# gol.net
KiCad netlist of a schematic drawn in EAGLE
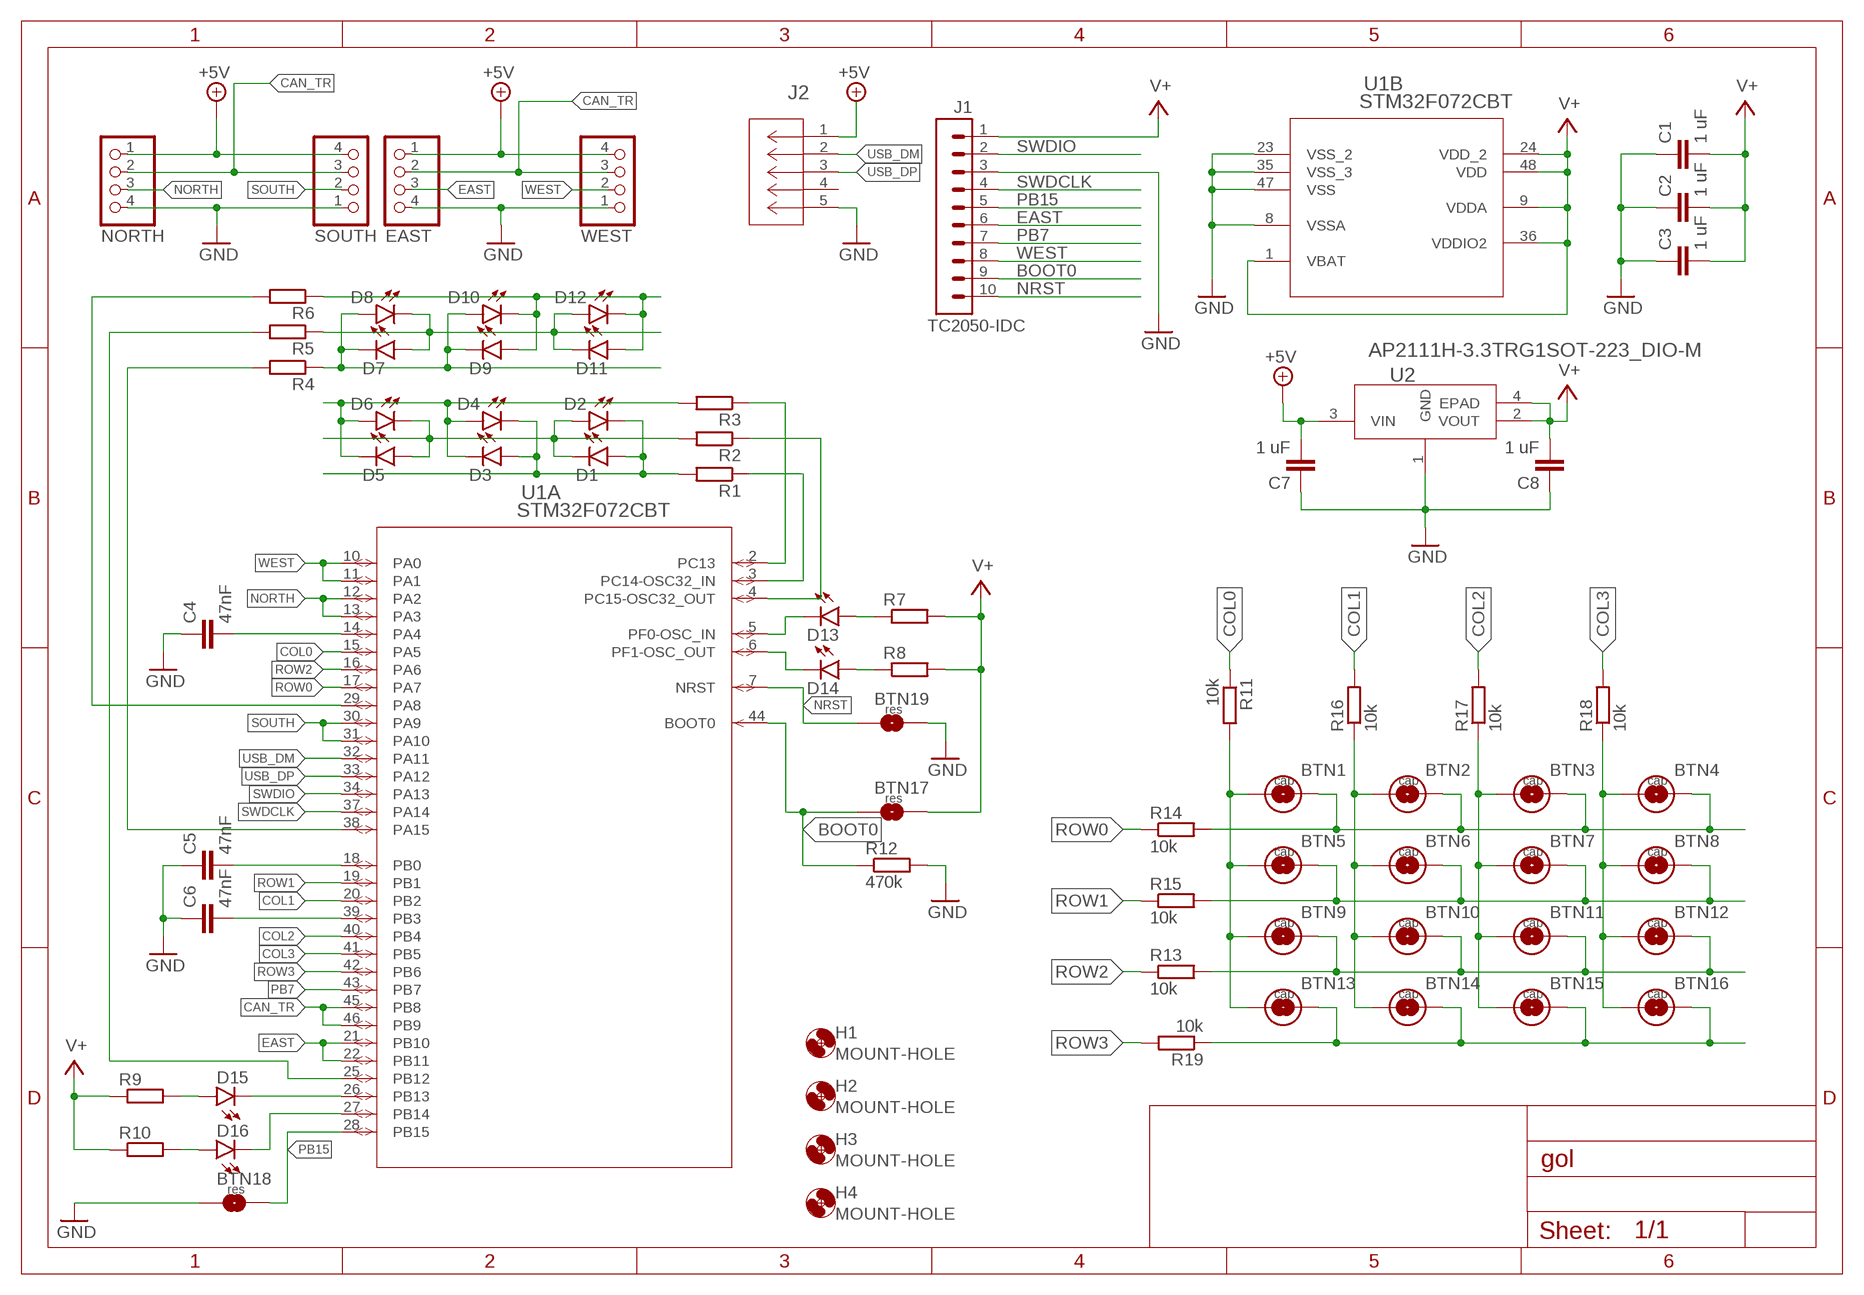
[diagram p0: schematic, sheet 1]

(export (version "E")
  (design (tool "Eeschema 10.0.6"))
  (components
    (comp (ref "BTN1")
      (value "BUTTON-CAP")
      (footprint "eagle-import:COMB")
      (libsource (lib "eagle-import") (part "BUTTON-CAP"))
    )
    (comp (ref "BTN2")
      (value "BUTTON-CAP")
      (footprint "eagle-import:COMB")
      (libsource (lib "eagle-import") (part "BUTTON-CAP"))
    )
    (comp (ref "BTN3")
      (value "BUTTON-CAP")
      (footprint "eagle-import:COMB")
      (libsource (lib "eagle-import") (part "BUTTON-CAP"))
    )
    (comp (ref "BTN4")
      (value "BUTTON-CAP")
      (footprint "eagle-import:COMB")
      (libsource (lib "eagle-import") (part "BUTTON-CAP"))
    )
    (comp (ref "BTN5")
      (value "BUTTON-CAP")
      (footprint "eagle-import:COMB")
      (libsource (lib "eagle-import") (part "BUTTON-CAP"))
    )
    (comp (ref "BTN6")
      (value "BUTTON-CAP")
      (footprint "eagle-import:COMB")
      (libsource (lib "eagle-import") (part "BUTTON-CAP"))
    )
    (comp (ref "BTN7")
      (value "BUTTON-CAP")
      (footprint "eagle-import:COMB")
      (libsource (lib "eagle-import") (part "BUTTON-CAP"))
    )
    (comp (ref "BTN8")
      (value "BUTTON-CAP")
      (footprint "eagle-import:COMB")
      (libsource (lib "eagle-import") (part "BUTTON-CAP"))
    )
    (comp (ref "BTN9")
      (value "BUTTON-CAP")
      (footprint "eagle-import:COMB")
      (libsource (lib "eagle-import") (part "BUTTON-CAP"))
    )
    (comp (ref "BTN10")
      (value "BUTTON-CAP")
      (footprint "eagle-import:COMB")
      (libsource (lib "eagle-import") (part "BUTTON-CAP"))
    )
    (comp (ref "BTN11")
      (value "BUTTON-CAP")
      (footprint "eagle-import:COMB")
      (libsource (lib "eagle-import") (part "BUTTON-CAP"))
    )
    (comp (ref "BTN12")
      (value "BUTTON-CAP")
      (footprint "eagle-import:COMB")
      (libsource (lib "eagle-import") (part "BUTTON-CAP"))
    )
    (comp (ref "BTN13")
      (value "BUTTON-CAP")
      (footprint "eagle-import:COMB")
      (libsource (lib "eagle-import") (part "BUTTON-CAP"))
    )
    (comp (ref "BTN14")
      (value "BUTTON-CAP")
      (footprint "eagle-import:COMB")
      (libsource (lib "eagle-import") (part "BUTTON-CAP"))
    )
    (comp (ref "BTN15")
      (value "BUTTON-CAP")
      (footprint "eagle-import:COMB")
      (libsource (lib "eagle-import") (part "BUTTON-CAP"))
    )
    (comp (ref "BTN16")
      (value "BUTTON-CAP")
      (footprint "eagle-import:COMB")
      (libsource (lib "eagle-import") (part "BUTTON-CAP"))
    )
    (comp (ref "BTN17")
      (value "FLASH")
      (footprint "eagle-import:COMB_EXPOSED")
      (libsource (lib "eagle-import") (part "BUTTON-RES"))
    )
    (comp (ref "BTN18")
      (value "MENU")
      (footprint "eagle-import:COMB_EXPOSED")
      (libsource (lib "eagle-import") (part "BUTTON-RES"))
    )
    (comp (ref "BTN19")
      (value "RESET")
      (footprint "eagle-import:COMB_EXPOSED")
      (libsource (lib "eagle-import") (part "BUTTON-RES"))
    )
    (comp (ref "C1")
      (value "1 uF")
      (footprint "eagle-import:C0603")
      (libsource (lib "eagle-import") (part "C-EUC0603"))
    )
    (comp (ref "C2")
      (value "1 uF")
      (footprint "eagle-import:C0603")
      (libsource (lib "eagle-import") (part "C-EUC0603"))
    )
    (comp (ref "C3")
      (value "1 uF")
      (footprint "eagle-import:C0603")
      (libsource (lib "eagle-import") (part "C-EUC0603"))
    )
    (comp (ref "C4")
      (value "47nF")
      (footprint "eagle-import:C0603")
      (libsource (lib "eagle-import") (part "C-EUC0603"))
    )
    (comp (ref "C5")
      (value "47nF")
      (footprint "eagle-import:C0603")
      (libsource (lib "eagle-import") (part "C-EUC0603"))
    )
    (comp (ref "C6")
      (value "47nF")
      (footprint "eagle-import:C0603")
      (libsource (lib "eagle-import") (part "C-EUC0603"))
    )
    (comp (ref "C7")
      (value "1 uF")
      (footprint "eagle-import:C0603")
      (libsource (lib "eagle-import") (part "C-EUC0603"))
    )
    (comp (ref "C8")
      (value "1 uF")
      (footprint "eagle-import:C0603")
      (libsource (lib "eagle-import") (part "C-EUC0603"))
    )
    (comp (ref "D1")
      (value "LED-5MM")
      (footprint "eagle-import:LED5MM")
      (libsource (lib "eagle-import") (part "LED-5MM"))
    )
    (comp (ref "D2")
      (value "LED-5MM")
      (footprint "eagle-import:LED5MM")
      (libsource (lib "eagle-import") (part "LED-5MM"))
    )
    (comp (ref "D3")
      (value "LED-5MM")
      (footprint "eagle-import:LED5MM")
      (libsource (lib "eagle-import") (part "LED-5MM"))
    )
    (comp (ref "D4")
      (value "LED-5MM")
      (footprint "eagle-import:LED5MM")
      (libsource (lib "eagle-import") (part "LED-5MM"))
    )
    (comp (ref "D5")
      (value "LED-5MM")
      (footprint "eagle-import:LED5MM")
      (libsource (lib "eagle-import") (part "LED-5MM"))
    )
    (comp (ref "D6")
      (value "LED-5MM")
      (footprint "eagle-import:LED5MM")
      (libsource (lib "eagle-import") (part "LED-5MM"))
    )
    (comp (ref "D7")
      (value "LED-5MM")
      (footprint "eagle-import:LED5MM")
      (libsource (lib "eagle-import") (part "LED-5MM"))
    )
    (comp (ref "D8")
      (value "LED-5MM")
      (footprint "eagle-import:LED5MM")
      (libsource (lib "eagle-import") (part "LED-5MM"))
    )
    (comp (ref "D9")
      (value "LED-5MM")
      (footprint "eagle-import:LED5MM")
      (libsource (lib "eagle-import") (part "LED-5MM"))
    )
    (comp (ref "D10")
      (value "LED-5MM")
      (footprint "eagle-import:LED5MM")
      (libsource (lib "eagle-import") (part "LED-5MM"))
    )
    (comp (ref "D11")
      (value "LED-5MM")
      (footprint "eagle-import:LED5MM")
      (libsource (lib "eagle-import") (part "LED-5MM"))
    )
    (comp (ref "D12")
      (value "LED-5MM")
      (footprint "eagle-import:LED5MM")
      (libsource (lib "eagle-import") (part "LED-5MM"))
    )
    (comp (ref "D13")
      (value "LED-5MM")
      (footprint "eagle-import:LED5MM")
      (libsource (lib "eagle-import") (part "LED-5MM"))
    )
    (comp (ref "D14")
      (value "LED-5MM")
      (footprint "eagle-import:LED5MM")
      (libsource (lib "eagle-import") (part "LED-5MM"))
    )
    (comp (ref "D15")
      (value "LED-5MM")
      (footprint "eagle-import:LED5MM")
      (libsource (lib "eagle-import") (part "LED-5MM"))
    )
    (comp (ref "D16")
      (value "LED-5MM")
      (footprint "eagle-import:LED5MM")
      (libsource (lib "eagle-import") (part "LED-5MM"))
    )
    (comp (ref "EAST")
      (value "EAST")
      (footprint "eagle-import:1X04")
      (libsource (lib "eagle-import") (part "PINHD-1X04"))
    )
    (comp (ref "H1")
      (value "MOUNT-HOLE")
      (footprint "eagle-import:MOUNT-HOLE-2,8")
      (libsource (lib "eagle-import") (part "MOUNT-HOLE"))
    )
    (comp (ref "H2")
      (value "MOUNT-HOLE")
      (footprint "eagle-import:MOUNT-HOLE-2,8")
      (libsource (lib "eagle-import") (part "MOUNT-HOLE"))
    )
    (comp (ref "H3")
      (value "MOUNT-HOLE")
      (footprint "eagle-import:MOUNT-HOLE-2,8")
      (libsource (lib "eagle-import") (part "MOUNT-HOLE"))
    )
    (comp (ref "H4")
      (value "MOUNT-HOLE")
      (footprint "eagle-import:MOUNT-HOLE-2,8")
      (libsource (lib "eagle-import") (part "MOUNT-HOLE"))
    )
    (comp (ref "J1")
      (value "TC2050-IDC")
      (footprint "eagle-import:TC2050-IDC")
      (libsource (lib "eagle-import") (part "TC2050-IDC"))
    )
    (comp (ref "J2")
      (value "2057-MCR-B-S-RA-TSMT-NP-CS4-T/RCT-ND")
      (footprint "eagle-import:CONN_10118192-0002LF_AMP")
      (fields
        (field (name "MANUFACTURER_PART_NUMBER") "10118192-0002LF")
        (field (name "COPYRIGHT") "Copyright (C) 2023 Ultra Librarian. All rights reserved.")
      )
      (libsource (lib "eagle-import") (part "10118192-0002LFCONN_10118192-0002LF_AMP"))
    )
    (comp (ref "NORTH")
      (value "NORTH")
      (footprint "eagle-import:JP4-RA-FEM")
      (libsource (lib "eagle-import") (part "PINHD-1X041X04-RA-FEM"))
    )
    (comp (ref "R1")
      (value "R-EU-0207/8")
      (footprint "eagle-import:0207_8")
      (libsource (lib "eagle-import") (part "R-EU-0207/8"))
    )
    (comp (ref "R2")
      (value "R-EU-0207/8")
      (footprint "eagle-import:0207_8")
      (libsource (lib "eagle-import") (part "R-EU-0207/8"))
    )
    (comp (ref "R3")
      (value "R-EU-0207/8")
      (footprint "eagle-import:0207_8")
      (libsource (lib "eagle-import") (part "R-EU-0207/8"))
    )
    (comp (ref "R4")
      (value "R-EU-0207/8")
      (footprint "eagle-import:0207_8")
      (libsource (lib "eagle-import") (part "R-EU-0207/8"))
    )
    (comp (ref "R5")
      (value "R-EU-0207/8")
      (footprint "eagle-import:0207_8")
      (libsource (lib "eagle-import") (part "R-EU-0207/8"))
    )
    (comp (ref "R6")
      (value "R-EU-0207/8")
      (footprint "eagle-import:0207_8")
      (libsource (lib "eagle-import") (part "R-EU-0207/8"))
    )
    (comp (ref "R7")
      (value "R-EU-0207/8")
      (footprint "eagle-import:0207_8")
      (libsource (lib "eagle-import") (part "R-EU-0207/8"))
    )
    (comp (ref "R8")
      (value "R-EU-0207/8")
      (footprint "eagle-import:0207_8")
      (libsource (lib "eagle-import") (part "R-EU-0207/8"))
    )
    (comp (ref "R9")
      (value "R-EU-0207/8")
      (footprint "eagle-import:0207_8")
      (libsource (lib "eagle-import") (part "R-EU-0207/8"))
    )
    (comp (ref "R10")
      (value "R-EU-0207/8")
      (footprint "eagle-import:0207_8")
      (libsource (lib "eagle-import") (part "R-EU-0207/8"))
    )
    (comp (ref "R11")
      (value "10k")
      (footprint "eagle-import:R0603")
      (libsource (lib "eagle-import") (part "R-EU_R0603"))
    )
    (comp (ref "R12")
      (value "470k")
      (footprint "eagle-import:R0603")
      (libsource (lib "eagle-import") (part "R-EU_R0603"))
    )
    (comp (ref "R13")
      (value "10k")
      (footprint "eagle-import:R0603")
      (libsource (lib "eagle-import") (part "R-EU_R0603"))
    )
    (comp (ref "R14")
      (value "10k")
      (footprint "eagle-import:R0603")
      (libsource (lib "eagle-import") (part "R-EU_R0603"))
    )
    (comp (ref "R15")
      (value "10k")
      (footprint "eagle-import:R0603")
      (libsource (lib "eagle-import") (part "R-EU_R0603"))
    )
    (comp (ref "R16")
      (value "10k")
      (footprint "eagle-import:R0603")
      (libsource (lib "eagle-import") (part "R-EU_R0603"))
    )
    (comp (ref "R17")
      (value "10k")
      (footprint "eagle-import:R0603")
      (libsource (lib "eagle-import") (part "R-EU_R0603"))
    )
    (comp (ref "R18")
      (value "10k")
      (footprint "eagle-import:R0603")
      (libsource (lib "eagle-import") (part "R-EU_R0603"))
    )
    (comp (ref "R19")
      (value "10k")
      (footprint "eagle-import:R0603")
      (libsource (lib "eagle-import") (part "R-EU_R0603"))
    )
    (comp (ref "SOUTH")
      (value "SOUTH")
      (footprint "eagle-import:1X04_90")
      (libsource (lib "eagle-import") (part "PINHD-1X4/90"))
    )
    (comp (ref "U1")
      (value "STM32F072CBT")
      (footprint "eagle-import:LQFP48-7X7MM")
      (fields
        (field (name "MANUFACTURER_PART_NUMBER") "STM32F072CBT6")
        (field (name "COPYRIGHT") "Copyright (C) 2023 Ultra Librarian. All rights reserved.")
      )
      (libsource (lib "eagle-import") (part "STM32F072CBT6LQFP48-7X7MM"))
    )
    (comp (ref "U2")
      (value "AP2111H-3.3TRG1SOT-223_DIO-M")
      (footprint "eagle-import:SOT-223_DIO-M")
      (fields
        (field (name "MANUFACTURER_PART_NUMBER") "AP2111H-3.3TRG1")
        (field (name "COPYRIGHT") "Copyright (C) 2023 Ultra Librarian. All rights reserved.")
      )
      (libsource (lib "eagle-import") (part "AP2111H-3.3TRG1SOT-223_DIO-M"))
    )
    (comp (ref "WEST")
      (value "WEST")
      (footprint "eagle-import:1X04")
      (libsource (lib "eagle-import") (part "PINHD-1X04"))
    )
  )
  (nets
    (net (code "1") (name "+5V") (class "Default")
      (node (ref "C7") (pin "2") (pinfunction "2_2") (pintype "passive"))
      (node (ref "EAST") (pin "1") (pinfunction "1_1") (pintype "passive"))
      (node (ref "J2") (pin "1") (pinfunction "1_1") (pintype "passive"))
      (node (ref "NORTH") (pin "1") (pinfunction "1_1") (pintype "passive"))
      (node (ref "SOUTH") (pin "4") (pinfunction "4_4") (pintype "passive"))
      (node (ref "U2") (pin "3") (pinfunction "VIN_3") (pintype "input"))
      (node (ref "WEST") (pin "4") (pinfunction "4_4") (pintype "passive"))
    )
    (net (code "2") (name "BOOT0") (class "Default")
      (node (ref "BTN17") (pin "P$1") (pinfunction "1_P$1") (pintype "passive"))
      (node (ref "J1") (pin "9") (pinfunction "9_9") (pintype "passive"))
      (node (ref "R12") (pin "1") (pinfunction "1_1") (pintype "passive"))
      (node (ref "U1") (pin "44") (pinfunction "BOOT0_44") (pintype "input"))
    )
    (net (code "3") (name "CAN_TR") (class "Default")
      (node (ref "EAST") (pin "2") (pinfunction "2_2") (pintype "passive"))
      (node (ref "NORTH") (pin "2") (pinfunction "2_2") (pintype "passive"))
      (node (ref "SOUTH") (pin "3") (pinfunction "3_3") (pintype "passive"))
      (node (ref "U1") (pin "45") (pinfunction "PB8_45") (pintype "bidirectional"))
      (node (ref "U1") (pin "46") (pinfunction "PB9_46") (pintype "bidirectional"))
      (node (ref "WEST") (pin "3") (pinfunction "3_3") (pintype "passive"))
    )
    (net (code "4") (name "COL0") (class "Default")
      (node (ref "R11") (pin "1") (pinfunction "1_1") (pintype "passive"))
      (node (ref "U1") (pin "15") (pinfunction "PA5_15") (pintype "bidirectional"))
    )
    (net (code "5") (name "COL1") (class "Default")
      (node (ref "R16") (pin "2") (pinfunction "2_2") (pintype "passive"))
      (node (ref "U1") (pin "20") (pinfunction "PB2_20") (pintype "bidirectional"))
    )
    (net (code "6") (name "COL2") (class "Default")
      (node (ref "R17") (pin "2") (pinfunction "2_2") (pintype "passive"))
      (node (ref "U1") (pin "40") (pinfunction "PB4_40") (pintype "bidirectional"))
    )
    (net (code "7") (name "COL3") (class "Default")
      (node (ref "R18") (pin "2") (pinfunction "2_2") (pintype "passive"))
      (node (ref "U1") (pin "41") (pinfunction "PB5_41") (pintype "bidirectional"))
    )
    (net (code "8") (name "EAST") (class "Default")
      (node (ref "EAST") (pin "3") (pinfunction "3_3") (pintype "passive"))
      (node (ref "J1") (pin "6") (pinfunction "6_6") (pintype "passive"))
      (node (ref "U1") (pin "21") (pinfunction "PB10_21") (pintype "bidirectional"))
      (node (ref "U1") (pin "22") (pinfunction "PB11_22") (pintype "bidirectional"))
    )
    (net (code "9") (name "GND") (class "Default")
      (node (ref "BTN18") (pin "P$1") (pinfunction "1_P$1") (pintype "passive"))
      (node (ref "BTN19") (pin "P$2") (pinfunction "2_P$2") (pintype "passive"))
      (node (ref "C1") (pin "1") (pinfunction "1_1") (pintype "passive"))
      (node (ref "C2") (pin "1") (pinfunction "1_1") (pintype "passive"))
      (node (ref "C3") (pin "1") (pinfunction "1_1") (pintype "passive"))
      (node (ref "C4") (pin "1") (pinfunction "1_1") (pintype "passive"))
      (node (ref "C5") (pin "1") (pinfunction "1_1") (pintype "passive"))
      (node (ref "C6") (pin "1") (pinfunction "1_1") (pintype "passive"))
      (node (ref "C7") (pin "1") (pinfunction "1_1") (pintype "passive"))
      (node (ref "C8") (pin "1") (pinfunction "1_1") (pintype "passive"))
      (node (ref "EAST") (pin "4") (pinfunction "4_4") (pintype "passive"))
      (node (ref "J1") (pin "3") (pinfunction "3_3") (pintype "passive"))
      (node (ref "J2") (pin "5") (pinfunction "5_5") (pintype "passive"))
      (node (ref "NORTH") (pin "4") (pinfunction "4_4") (pintype "passive"))
      (node (ref "R12") (pin "2") (pinfunction "2_2") (pintype "passive"))
      (node (ref "SOUTH") (pin "1") (pinfunction "1_1") (pintype "passive"))
      (node (ref "U1") (pin "23") (pinfunction "VSS_2_23") (pintype "power_in"))
      (node (ref "U1") (pin "35") (pinfunction "VSS_3_35") (pintype "power_in"))
      (node (ref "U1") (pin "47") (pinfunction "VSS_47") (pintype "power_in"))
      (node (ref "U1") (pin "8") (pinfunction "VSSA_8") (pintype "power_in"))
      (node (ref "U2") (pin "1") (pinfunction "GND_1") (pintype "power_in"))
      (node (ref "WEST") (pin "1") (pinfunction "1_1") (pintype "passive"))
    )
    (net (code "10") (name "NORTH") (class "Default")
      (node (ref "NORTH") (pin "3") (pinfunction "3_3") (pintype "passive"))
      (node (ref "U1") (pin "12") (pinfunction "PA2_12") (pintype "bidirectional"))
      (node (ref "U1") (pin "13") (pinfunction "PA3_13") (pintype "bidirectional"))
    )
    (net (code "11") (name "NRST") (class "Default")
      (node (ref "BTN19") (pin "P$1") (pinfunction "1_P$1") (pintype "passive"))
      (node (ref "J1") (pin "10") (pinfunction "10_10") (pintype "passive"))
      (node (ref "U1") (pin "7") (pinfunction "NRST_7") (pintype "bidirectional"))
    )
    (net (code "12") (name "Net-(BTN1-1)") (class "Default")
      (node (ref "BTN1") (pin "P$1") (pinfunction "1_P$1") (pintype "passive"))
      (node (ref "BTN13") (pin "P$1") (pinfunction "1_P$1") (pintype "passive"))
      (node (ref "BTN5") (pin "P$1") (pinfunction "1_P$1") (pintype "passive"))
      (node (ref "BTN9") (pin "P$1") (pinfunction "1_P$1") (pintype "passive"))
      (node (ref "R11") (pin "2") (pinfunction "2_2") (pintype "passive"))
    )
    (net (code "13") (name "Net-(BTN1-2)") (class "Default")
      (node (ref "BTN1") (pin "P$2") (pinfunction "2_P$2") (pintype "passive"))
      (node (ref "BTN2") (pin "P$2") (pinfunction "2_P$2") (pintype "passive"))
      (node (ref "BTN3") (pin "P$2") (pinfunction "2_P$2") (pintype "passive"))
      (node (ref "BTN4") (pin "P$2") (pinfunction "2_P$2") (pintype "passive"))
      (node (ref "R14") (pin "2") (pinfunction "2_2") (pintype "passive"))
    )
    (net (code "14") (name "Net-(BTN5-2)") (class "Default")
      (node (ref "BTN5") (pin "P$2") (pinfunction "2_P$2") (pintype "passive"))
      (node (ref "BTN6") (pin "P$2") (pinfunction "2_P$2") (pintype "passive"))
      (node (ref "BTN7") (pin "P$2") (pinfunction "2_P$2") (pintype "passive"))
      (node (ref "BTN8") (pin "P$2") (pinfunction "2_P$2") (pintype "passive"))
      (node (ref "R15") (pin "2") (pinfunction "2_2") (pintype "passive"))
    )
    (net (code "15") (name "Net-(BTN10-1)") (class "Default")
      (node (ref "BTN10") (pin "P$1") (pinfunction "1_P$1") (pintype "passive"))
      (node (ref "BTN14") (pin "P$1") (pinfunction "1_P$1") (pintype "passive"))
      (node (ref "BTN2") (pin "P$1") (pinfunction "1_P$1") (pintype "passive"))
      (node (ref "BTN6") (pin "P$1") (pinfunction "1_P$1") (pintype "passive"))
      (node (ref "R16") (pin "1") (pinfunction "1_1") (pintype "passive"))
    )
    (net (code "16") (name "Net-(BTN10-2)") (class "Default")
      (node (ref "BTN10") (pin "P$2") (pinfunction "2_P$2") (pintype "passive"))
      (node (ref "BTN11") (pin "P$2") (pinfunction "2_P$2") (pintype "passive"))
      (node (ref "BTN12") (pin "P$2") (pinfunction "2_P$2") (pintype "passive"))
      (node (ref "BTN9") (pin "P$2") (pinfunction "2_P$2") (pintype "passive"))
      (node (ref "R13") (pin "2") (pinfunction "2_2") (pintype "passive"))
    )
    (net (code "17") (name "Net-(BTN11-1)") (class "Default")
      (node (ref "BTN11") (pin "P$1") (pinfunction "1_P$1") (pintype "passive"))
      (node (ref "BTN15") (pin "P$1") (pinfunction "1_P$1") (pintype "passive"))
      (node (ref "BTN3") (pin "P$1") (pinfunction "1_P$1") (pintype "passive"))
      (node (ref "BTN7") (pin "P$1") (pinfunction "1_P$1") (pintype "passive"))
      (node (ref "R17") (pin "1") (pinfunction "1_1") (pintype "passive"))
    )
    (net (code "18") (name "Net-(BTN12-1)") (class "Default")
      (node (ref "BTN12") (pin "P$1") (pinfunction "1_P$1") (pintype "passive"))
      (node (ref "BTN16") (pin "P$1") (pinfunction "1_P$1") (pintype "passive"))
      (node (ref "BTN4") (pin "P$1") (pinfunction "1_P$1") (pintype "passive"))
      (node (ref "BTN8") (pin "P$1") (pinfunction "1_P$1") (pintype "passive"))
      (node (ref "R18") (pin "1") (pinfunction "1_1") (pintype "passive"))
    )
    (net (code "19") (name "Net-(BTN13-2)") (class "Default")
      (node (ref "BTN13") (pin "P$2") (pinfunction "2_P$2") (pintype "passive"))
      (node (ref "BTN14") (pin "P$2") (pinfunction "2_P$2") (pintype "passive"))
      (node (ref "BTN15") (pin "P$2") (pinfunction "2_P$2") (pintype "passive"))
      (node (ref "BTN16") (pin "P$2") (pinfunction "2_P$2") (pintype "passive"))
      (node (ref "R19") (pin "1") (pinfunction "1_1") (pintype "passive"))
    )
    (net (code "20") (name "Net-(D1-C)") (class "Default")
      (node (ref "D1") (pin "K") (pinfunction "C_K") (pintype "passive"))
      (node (ref "D2") (pin "A") (pinfunction "A_A") (pintype "passive"))
      (node (ref "D5") (pin "A") (pinfunction "A_A") (pintype "passive"))
      (node (ref "D6") (pin "K") (pinfunction "C_K") (pintype "passive"))
      (node (ref "R2") (pin "2") (pinfunction "2_2") (pintype "passive"))
    )
    (net (code "21") (name "Net-(D2-C)") (class "Default")
      (node (ref "D1") (pin "A") (pinfunction "A_A") (pintype "passive"))
      (node (ref "D2") (pin "K") (pinfunction "C_K") (pintype "passive"))
      (node (ref "D3") (pin "A") (pinfunction "A_A") (pintype "passive"))
      (node (ref "D4") (pin "K") (pinfunction "C_K") (pintype "passive"))
      (node (ref "R1") (pin "2") (pinfunction "2_2") (pintype "passive"))
    )
    (net (code "22") (name "Net-(D3-C)") (class "Default")
      (node (ref "D3") (pin "K") (pinfunction "C_K") (pintype "passive"))
      (node (ref "D4") (pin "A") (pinfunction "A_A") (pintype "passive"))
      (node (ref "D5") (pin "K") (pinfunction "C_K") (pintype "passive"))
      (node (ref "D6") (pin "A") (pinfunction "A_A") (pintype "passive"))
      (node (ref "R3") (pin "2") (pinfunction "2_2") (pintype "passive"))
    )
    (net (code "23") (name "Net-(D7-C)") (class "Default")
      (node (ref "D10") (pin "A") (pinfunction "A_A") (pintype "passive"))
      (node (ref "D7") (pin "K") (pinfunction "C_K") (pintype "passive"))
      (node (ref "D8") (pin "A") (pinfunction "A_A") (pintype "passive"))
      (node (ref "D9") (pin "K") (pinfunction "C_K") (pintype "passive"))
      (node (ref "R4") (pin "1") (pinfunction "1_1") (pintype "passive"))
    )
    (net (code "24") (name "Net-(D10-C)") (class "Default")
      (node (ref "D10") (pin "K") (pinfunction "C_K") (pintype "passive"))
      (node (ref "D11") (pin "A") (pinfunction "A_A") (pintype "passive"))
      (node (ref "D12") (pin "K") (pinfunction "C_K") (pintype "passive"))
      (node (ref "D9") (pin "A") (pinfunction "A_A") (pintype "passive"))
      (node (ref "R6") (pin "1") (pinfunction "1_1") (pintype "passive"))
    )
    (net (code "25") (name "Net-(D11-C)") (class "Default")
      (node (ref "D11") (pin "K") (pinfunction "C_K") (pintype "passive"))
      (node (ref "D12") (pin "A") (pinfunction "A_A") (pintype "passive"))
      (node (ref "D7") (pin "A") (pinfunction "A_A") (pintype "passive"))
      (node (ref "D8") (pin "K") (pinfunction "C_K") (pintype "passive"))
      (node (ref "R5") (pin "1") (pinfunction "1_1") (pintype "passive"))
    )
    (net (code "26") (name "Net-(D13-C)") (class "Default")
      (node (ref "D13") (pin "K") (pinfunction "C_K") (pintype "passive"))
      (node (ref "U1") (pin "5") (pinfunction "PF0-OSC_IN_5") (pintype "bidirectional"))
    )
    (net (code "27") (name "Net-(D13-PadA)") (class "Default")
      (node (ref "D13") (pin "A") (pinfunction "A_A") (pintype "passive"))
      (node (ref "R7") (pin "1") (pinfunction "1_1") (pintype "passive"))
    )
    (net (code "28") (name "Net-(D14-C)") (class "Default")
      (node (ref "D14") (pin "K") (pinfunction "C_K") (pintype "passive"))
      (node (ref "U1") (pin "6") (pinfunction "PF1-OSC_OUT_6") (pintype "bidirectional"))
    )
    (net (code "29") (name "Net-(D14-PadA)") (class "Default")
      (node (ref "D14") (pin "A") (pinfunction "A_A") (pintype "passive"))
      (node (ref "R8") (pin "1") (pinfunction "1_1") (pintype "passive"))
    )
    (net (code "30") (name "Net-(D15-C)") (class "Default")
      (node (ref "D15") (pin "K") (pinfunction "C_K") (pintype "passive"))
      (node (ref "U1") (pin "26") (pinfunction "PB13_26") (pintype "bidirectional"))
    )
    (net (code "31") (name "Net-(D15-PadA)") (class "Default")
      (node (ref "D15") (pin "A") (pinfunction "A_A") (pintype "passive"))
      (node (ref "R9") (pin "2") (pinfunction "2_2") (pintype "passive"))
    )
    (net (code "32") (name "Net-(D16-C)") (class "Default")
      (node (ref "D16") (pin "K") (pinfunction "C_K") (pintype "passive"))
      (node (ref "U1") (pin "27") (pinfunction "PB14_27") (pintype "bidirectional"))
    )
    (net (code "33") (name "Net-(D16-PadA)") (class "Default")
      (node (ref "D16") (pin "A") (pinfunction "A_A") (pintype "passive"))
      (node (ref "R10") (pin "2") (pinfunction "2_2") (pintype "passive"))
    )
    (net (code "34") (name "Net-(U1A-PA4)") (class "Default")
      (node (ref "C4") (pin "2") (pinfunction "2_2") (pintype "passive"))
      (node (ref "U1") (pin "14") (pinfunction "PA4_14") (pintype "bidirectional"))
    )
    (net (code "35") (name "Net-(U1A-PA8)") (class "Default")
      (node (ref "R6") (pin "2") (pinfunction "2_2") (pintype "passive"))
      (node (ref "U1") (pin "29") (pinfunction "PA8_29") (pintype "bidirectional"))
    )
    (net (code "36") (name "Net-(U1A-PA15)") (class "Default")
      (node (ref "R4") (pin "2") (pinfunction "2_2") (pintype "passive"))
      (node (ref "U1") (pin "38") (pinfunction "PA15_38") (pintype "bidirectional"))
    )
    (net (code "37") (name "Net-(U1A-PB0)") (class "Default")
      (node (ref "C5") (pin "2") (pinfunction "2_2") (pintype "passive"))
      (node (ref "U1") (pin "18") (pinfunction "PB0_18") (pintype "bidirectional"))
    )
    (net (code "38") (name "Net-(U1A-PB3)") (class "Default")
      (node (ref "C6") (pin "2") (pinfunction "2_2") (pintype "passive"))
      (node (ref "U1") (pin "39") (pinfunction "PB3_39") (pintype "bidirectional"))
    )
    (net (code "39") (name "Net-(U1A-PB12)") (class "Default")
      (node (ref "R5") (pin "2") (pinfunction "2_2") (pintype "passive"))
      (node (ref "U1") (pin "25") (pinfunction "PB12_25") (pintype "bidirectional"))
    )
    (net (code "40") (name "Net-(U1A-PC13)") (class "Default")
      (node (ref "R3") (pin "1") (pinfunction "1_1") (pintype "passive"))
      (node (ref "U1") (pin "2") (pinfunction "PC13_2") (pintype "bidirectional"))
    )
    (net (code "41") (name "Net-(U1A-PC14-OSC32_IN)") (class "Default")
      (node (ref "R1") (pin "1") (pinfunction "1_1") (pintype "passive"))
      (node (ref "U1") (pin "3") (pinfunction "PC14-OSC32_IN_3") (pintype "bidirectional"))
    )
    (net (code "42") (name "Net-(U1A-PC15-OSC32_OUT)") (class "Default")
      (node (ref "R2") (pin "1") (pinfunction "1_1") (pintype "passive"))
      (node (ref "U1") (pin "4") (pinfunction "PC15-OSC32_OUT_4") (pintype "bidirectional"))
    )
    (net (code "43") (name "PB7") (class "Default")
      (node (ref "J1") (pin "7") (pinfunction "7_7") (pintype "passive"))
      (node (ref "U1") (pin "43") (pinfunction "PB7_43") (pintype "bidirectional"))
    )
    (net (code "44") (name "PB15") (class "Default")
      (node (ref "BTN18") (pin "P$2") (pinfunction "2_P$2") (pintype "passive"))
      (node (ref "J1") (pin "5") (pinfunction "5_5") (pintype "passive"))
      (node (ref "U1") (pin "28") (pinfunction "PB15_28") (pintype "bidirectional"))
    )
    (net (code "45") (name "ROW0") (class "Default")
      (node (ref "R14") (pin "1") (pinfunction "1_1") (pintype "passive"))
      (node (ref "U1") (pin "17") (pinfunction "PA7_17") (pintype "bidirectional"))
    )
    (net (code "46") (name "ROW1") (class "Default")
      (node (ref "R15") (pin "1") (pinfunction "1_1") (pintype "passive"))
      (node (ref "U1") (pin "19") (pinfunction "PB1_19") (pintype "bidirectional"))
    )
    (net (code "47") (name "ROW2") (class "Default")
      (node (ref "R13") (pin "1") (pinfunction "1_1") (pintype "passive"))
      (node (ref "U1") (pin "16") (pinfunction "PA6_16") (pintype "bidirectional"))
    )
    (net (code "48") (name "ROW3") (class "Default")
      (node (ref "R19") (pin "2") (pinfunction "2_2") (pintype "passive"))
      (node (ref "U1") (pin "42") (pinfunction "PB6_42") (pintype "bidirectional"))
    )
    (net (code "49") (name "SOUTH") (class "Default")
      (node (ref "SOUTH") (pin "2") (pinfunction "2_2") (pintype "passive"))
      (node (ref "U1") (pin "30") (pinfunction "PA9_30") (pintype "bidirectional"))
      (node (ref "U1") (pin "31") (pinfunction "PA10_31") (pintype "bidirectional"))
    )
    (net (code "50") (name "SWDCLK") (class "Default")
      (node (ref "J1") (pin "4") (pinfunction "4_4") (pintype "passive"))
      (node (ref "U1") (pin "37") (pinfunction "PA14_37") (pintype "bidirectional"))
    )
    (net (code "51") (name "SWDIO") (class "Default")
      (node (ref "J1") (pin "2") (pinfunction "2_2") (pintype "passive"))
      (node (ref "U1") (pin "34") (pinfunction "PA13_34") (pintype "bidirectional"))
    )
    (net (code "52") (name "USB_DM") (class "Default")
      (node (ref "J2") (pin "2") (pinfunction "2_2") (pintype "passive"))
      (node (ref "U1") (pin "32") (pinfunction "PA11_32") (pintype "bidirectional"))
    )
    (net (code "53") (name "USB_DP") (class "Default")
      (node (ref "J2") (pin "3") (pinfunction "3_3") (pintype "passive"))
      (node (ref "U1") (pin "33") (pinfunction "PA12_33") (pintype "bidirectional"))
    )
    (net (code "54") (name "V+") (class "Default")
      (node (ref "BTN17") (pin "P$2") (pinfunction "2_P$2") (pintype "passive"))
      (node (ref "C1") (pin "2") (pinfunction "2_2") (pintype "passive"))
      (node (ref "C2") (pin "2") (pinfunction "2_2") (pintype "passive"))
      (node (ref "C3") (pin "2") (pinfunction "2_2") (pintype "passive"))
      (node (ref "C8") (pin "2") (pinfunction "2_2") (pintype "passive"))
      (node (ref "J1") (pin "1") (pinfunction "1_1") (pintype "passive"))
      (node (ref "R10") (pin "1") (pinfunction "1_1") (pintype "passive"))
      (node (ref "R7") (pin "2") (pinfunction "2_2") (pintype "passive"))
      (node (ref "R8") (pin "2") (pinfunction "2_2") (pintype "passive"))
      (node (ref "R9") (pin "1") (pinfunction "1_1") (pintype "passive"))
      (node (ref "U1") (pin "1") (pinfunction "VBAT_1") (pintype "power_in"))
      (node (ref "U1") (pin "24") (pinfunction "VDD_2_24") (pintype "power_in"))
      (node (ref "U1") (pin "36") (pinfunction "VDDIO2_36") (pintype "power_in"))
      (node (ref "U1") (pin "48") (pinfunction "VDD_48") (pintype "power_in"))
      (node (ref "U1") (pin "9") (pinfunction "VDDA_9") (pintype "power_in"))
      (node (ref "U2") (pin "2") (pinfunction "VOUT_2") (pintype "output"))
      (node (ref "U2") (pin "4") (pinfunction "EPAD_4") (pintype "passive"))
    )
    (net (code "55") (name "WEST") (class "Default")
      (node (ref "J1") (pin "8") (pinfunction "8_8") (pintype "passive"))
      (node (ref "U1") (pin "10") (pinfunction "PA0_10") (pintype "bidirectional"))
      (node (ref "U1") (pin "11") (pinfunction "PA1_11") (pintype "bidirectional"))
      (node (ref "WEST") (pin "2") (pinfunction "2_2") (pintype "passive"))
    )
    (net (code "56") (name "unconnected-(J2-Pad4)") (class "Default")
      (node (ref "J2") (pin "4") (pinfunction "4_4") (pintype "passive"))
    )
  )
)
